# SIM7600CE.net
KiCad netlist of a schematic drawn in Altium Designer
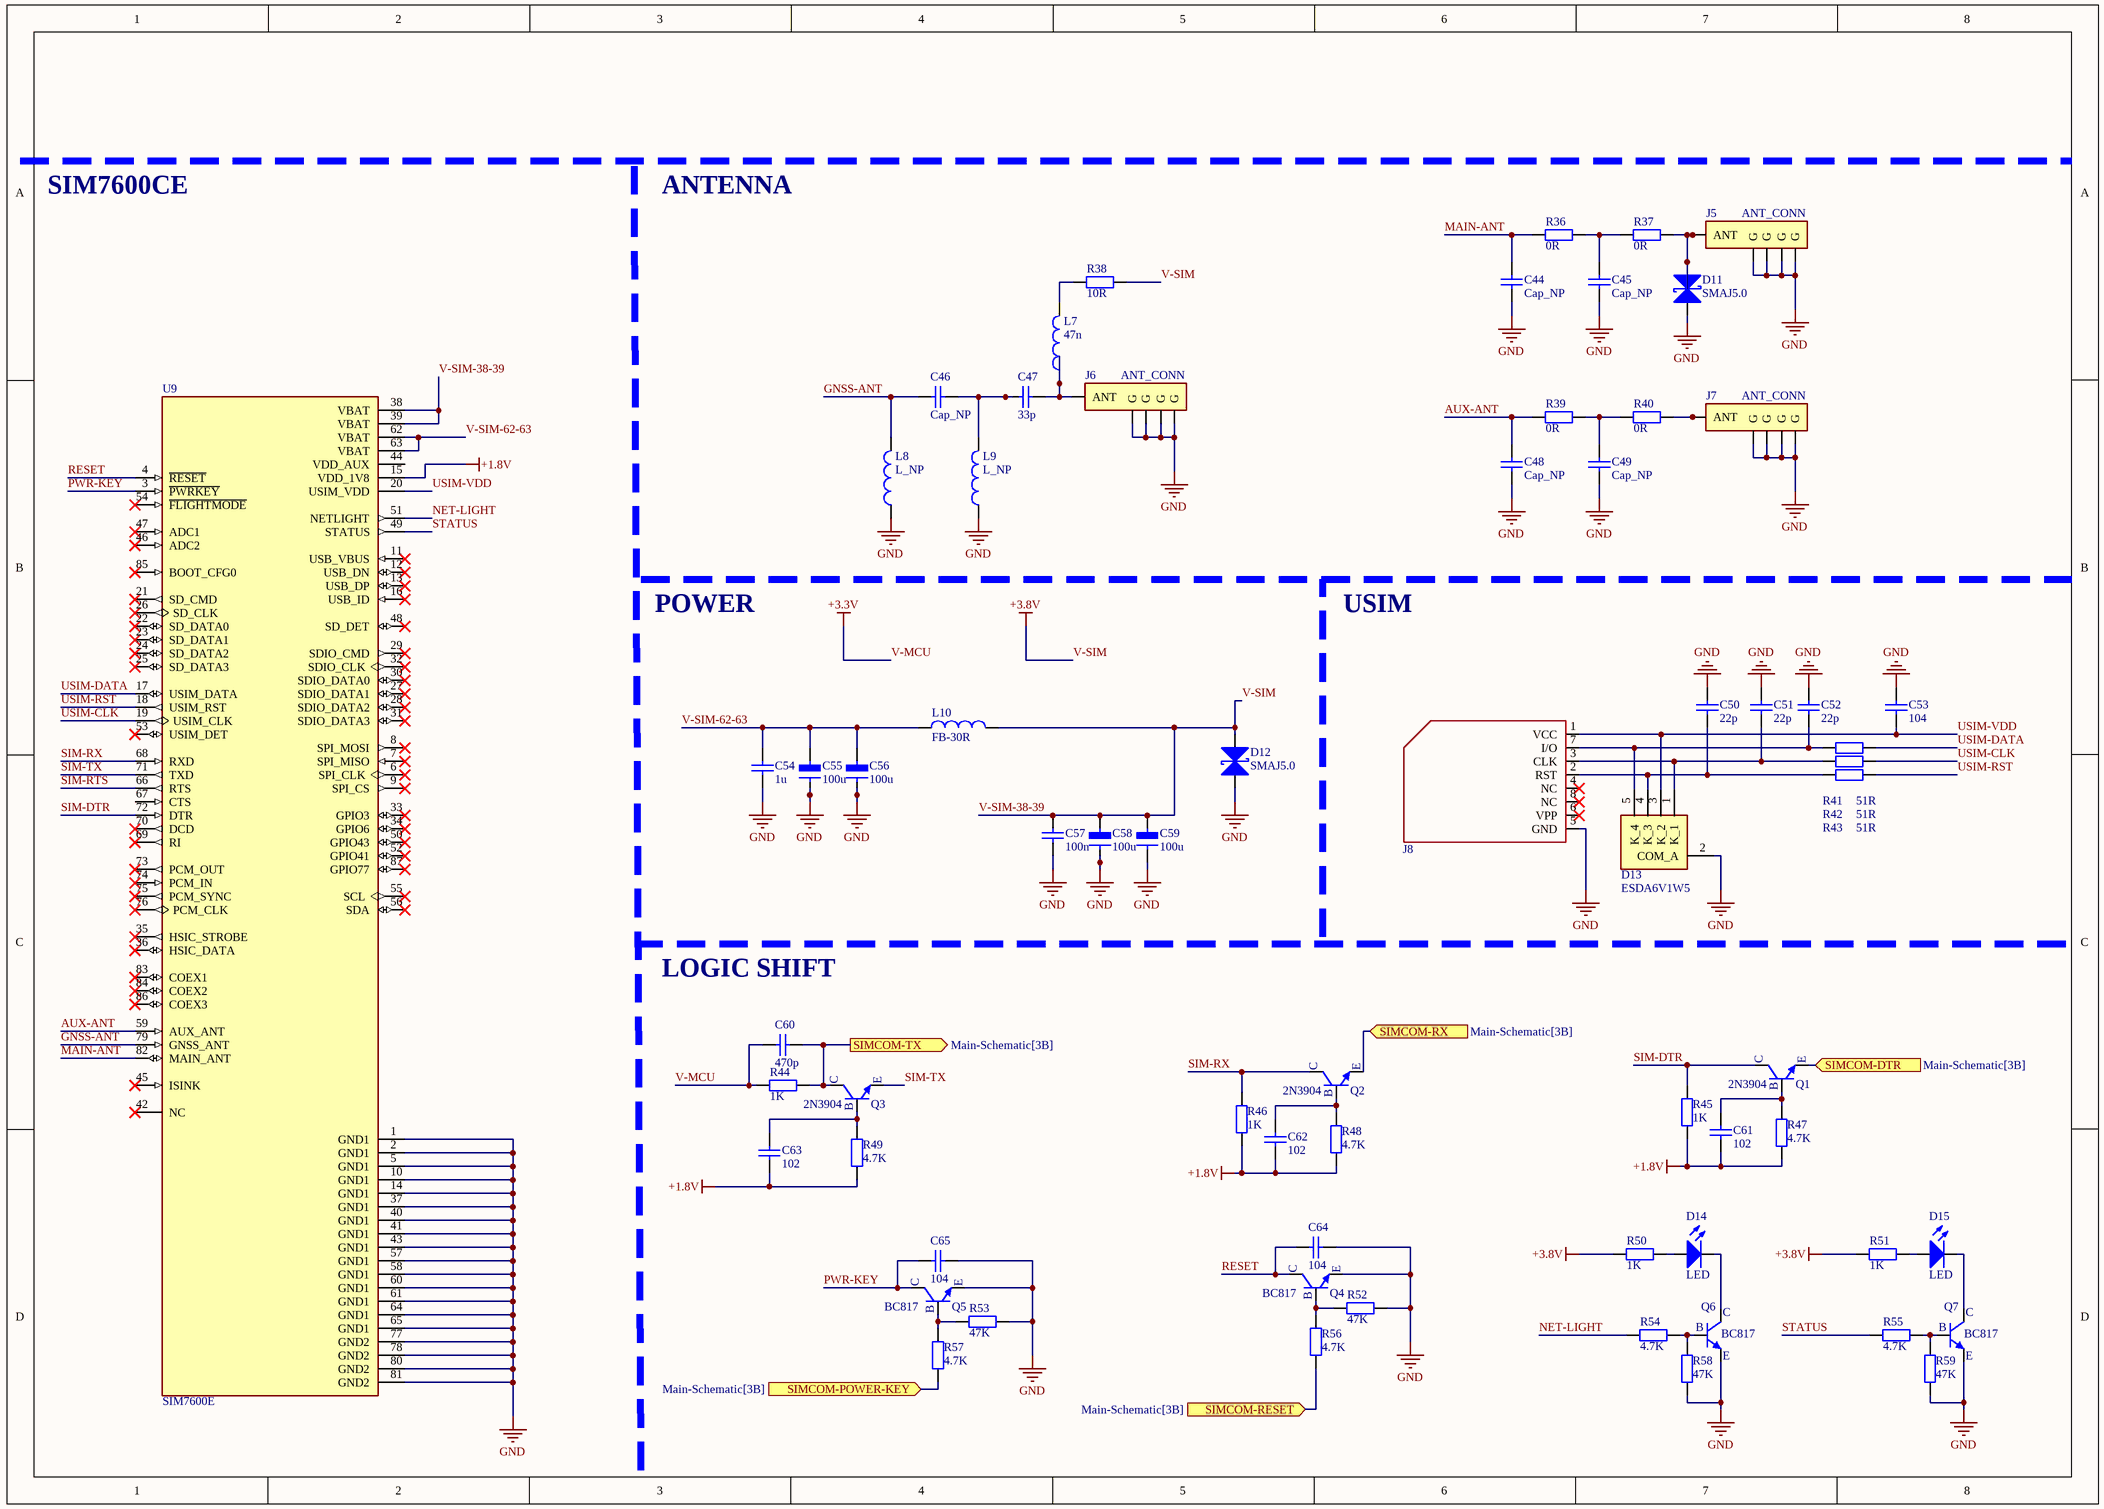
[diagram p0: SIM7600CE.SchDoc]

(export (version "E")
  (design (tool "Eeschema 10.0.6"))
  (components
    (comp (ref "C44")
      (value "Cap_NP")
      (footprint "CAP_0603")
      (description "Non-polarized capacitor")
      (libsource (lib "Capacitor") (part "Cap_NP"))
    )
    (comp (ref "C45")
      (value "Cap_NP")
      (footprint "CAP_0603")
      (description "Non-polarized capacitor")
      (libsource (lib "Capacitor") (part "Cap_NP"))
    )
    (comp (ref "C46")
      (value "Cap_NP")
      (footprint "CAP_0603")
      (description "Non-polarized capacitor")
      (libsource (lib "Capacitor") (part "Cap_NP"))
    )
    (comp (ref "C47")
      (value "33p")
      (footprint "CAP_0603")
      (description "Non-polarized capacitor")
      (libsource (lib "Capacitor") (part "Cap_NP"))
    )
    (comp (ref "C48")
      (value "Cap_NP")
      (footprint "CAP_0603")
      (description "Non-polarized capacitor")
      (libsource (lib "Capacitor") (part "Cap_NP"))
    )
    (comp (ref "C49")
      (value "Cap_NP")
      (footprint "CAP_0603")
      (description "Non-polarized capacitor")
      (libsource (lib "Capacitor") (part "Cap_NP"))
    )
    (comp (ref "C50")
      (value "22p")
      (footprint "CAP_0603")
      (description "Non-polarized capacitor")
      (libsource (lib "Capacitor") (part "Cap_NP"))
    )
    (comp (ref "C51")
      (value "22p")
      (footprint "CAP_0603")
      (description "Non-polarized capacitor")
      (libsource (lib "Capacitor") (part "Cap_NP"))
    )
    (comp (ref "C52")
      (value "22p")
      (footprint "CAP_0603")
      (description "Non-polarized capacitor")
      (libsource (lib "Capacitor") (part "Cap_NP"))
    )
    (comp (ref "C53")
      (value "104")
      (footprint "CAP_0603")
      (description "Non-polarized capacitor")
      (libsource (lib "Capacitor") (part "Cap_NP"))
    )
    (comp (ref "C54")
      (value "1u")
      (footprint "CAP_0603")
      (description "Non-polarized capacitor")
      (libsource (lib "Capacitor") (part "Cap_NP"))
    )
    (comp (ref "C55")
      (value "100u")
      (footprint "C_Tanta_B3528")
      (description "Polarized tantaLum capacitor")
      (libsource (lib "Capacitor") (part "Cap_Tatan"))
    )
    (comp (ref "C56")
      (value "100u")
      (footprint "C_Tanta_B3528")
      (description "Polarized tantaLum capacitor")
      (libsource (lib "Capacitor") (part "Cap_Tatan"))
    )
    (comp (ref "C57")
      (value "100n")
      (footprint "CAP_0603")
      (description "Non-polarized capacitor")
      (libsource (lib "Capacitor") (part "Cap_NP"))
    )
    (comp (ref "C58")
      (value "100u")
      (footprint "C_Tanta_B3528")
      (description "Polarized tantaLum capacitor")
      (libsource (lib "Capacitor") (part "Cap_Tatan"))
    )
    (comp (ref "C59")
      (value "100u")
      (footprint "C_Tanta_B3528")
      (description "Polarized tantaLum capacitor")
      (libsource (lib "Capacitor") (part "Cap_Tatan"))
    )
    (comp (ref "C60")
      (value "470p")
      (footprint "CAP_0603")
      (description "Non-polarized capacitor")
      (libsource (lib "Capacitor") (part "Cap_NP"))
    )
    (comp (ref "C61")
      (value "102")
      (footprint "CAP_0603")
      (description "Non-polarized capacitor")
      (libsource (lib "Capacitor") (part "Cap_NP"))
    )
    (comp (ref "C62")
      (value "102")
      (footprint "CAP_0603")
      (description "Non-polarized capacitor")
      (libsource (lib "Capacitor") (part "Cap_NP"))
    )
    (comp (ref "C63")
      (value "102")
      (footprint "CAP_0603")
      (description "Non-polarized capacitor")
      (libsource (lib "Capacitor") (part "Cap_NP"))
    )
    (comp (ref "C64")
      (value "104")
      (footprint "CAP_0603")
      (description "Non-polarized capacitor")
      (libsource (lib "Capacitor") (part "Cap_NP"))
    )
    (comp (ref "C65")
      (value "104")
      (footprint "CAP_0603")
      (description "Non-polarized capacitor")
      (libsource (lib "Capacitor") (part "Cap_NP"))
    )
    (comp (ref "D11")
      (value "SMAJ5.0")
      (footprint "SMA")
      (description "TVS diode")
      (libsource (lib "Diode") (part "TVS-Diode"))
    )
    (comp (ref "D12")
      (value "SMAJ5.0")
      (footprint "SMA")
      (description "TVS diode")
      (libsource (lib "Diode") (part "TVS-Diode"))
    )
    (comp (ref "D13")
      (value "ESDA6V1W5")
      (footprint "SOT65P210X110-5N")
      (description "Integrated Circuit")
      (fields (field (name "MOUSER PART NUMBER") "511-ESDA6V1W5"))
      (libsource (lib "SamacSys") (part "ESDA6V1W5"))
    )
    (comp (ref "D14")
      (value "LED")
      (footprint "LED-0805-Red")
      (description "Light Emitting Diode")
      (libsource (lib "Diode") (part "LED"))
    )
    (comp (ref "D15")
      (value "LED")
      (footprint "LED-0805-Red")
      (description "Light Emitting Diode")
      (libsource (lib "Diode") (part "LED"))
    )
    (comp (ref "J5")
      (value "ANT_CONN")
      (footprint "IPEX")
      (description "ATENNA PIN 1")
      (libsource (lib "Connector") (part "ANT_CONN"))
    )
    (comp (ref "J6")
      (value "ANT_CONN")
      (footprint "IPEX")
      (description "ATENNA PIN 1")
      (libsource (lib "Connector") (part "ANT_CONN"))
    )
    (comp (ref "J7")
      (value "ANT_CONN")
      (footprint "IPEX")
      (description "ATENNA PIN 1")
      (libsource (lib "Connector") (part "ANT_CONN"))
    )
    (comp (ref "J8")
      (value "MicroSimcard")
      (footprint "MICRO SIM SOCKET")
      (description "Micro Simcard Socket")
      (libsource (lib "VNT.Connector Socket") (part "MicroSimcard"))
    )
    (comp (ref "L7")
      (value "47n")
      (footprint "INDC-0805")
      (description "Inductor")
      (fields (field (name "PUBLISHER") "Altium Limited"))
      (libsource (lib "Inductor") (part "Inductor"))
    )
    (comp (ref "L8")
      (value "L_NP")
      (footprint "INDC-0805")
      (description "Inductor")
      (fields (field (name "PUBLISHER") "Altium Limited"))
      (libsource (lib "Inductor") (part "Inductor"))
    )
    (comp (ref "L9")
      (value "L_NP")
      (footprint "INDC-0805")
      (description "Inductor")
      (fields (field (name "PUBLISHER") "Altium Limited"))
      (libsource (lib "Inductor") (part "Inductor"))
    )
    (comp (ref "L10")
      (value "FB-30R")
      (footprint "INDC-0805")
      (description "Inductor")
      (fields (field (name "PUBLISHER") "Altium Limited"))
      (libsource (lib "Inductor") (part "Inductor"))
    )
    (comp (ref "Q1")
      (value "2N3904")
      (footprint "SOT-23")
      (libsource (lib "Transistor-FET-IGBT") (part "N-Trans"))
    )
    (comp (ref "Q2")
      (value "2N3904")
      (footprint "SOT-23")
      (libsource (lib "Transistor-FET-IGBT") (part "N-Trans"))
    )
    (comp (ref "Q3")
      (value "2N3904")
      (footprint "SOT-23")
      (libsource (lib "Transistor-FET-IGBT") (part "N-Trans"))
    )
    (comp (ref "Q4")
      (value "BC817")
      (footprint "SOT-23")
      (libsource (lib "Transistor-FET-IGBT") (part "N-Trans"))
    )
    (comp (ref "Q5")
      (value "BC817")
      (footprint "SOT-23")
      (libsource (lib "Transistor-FET-IGBT") (part "N-Trans"))
    )
    (comp (ref "Q6")
      (value "BC817")
      (footprint "SOT-23")
      (libsource (lib "Transistor-FET-IGBT") (part "N-Trans"))
    )
    (comp (ref "Q7")
      (value "BC817")
      (footprint "SOT-23")
      (libsource (lib "Transistor-FET-IGBT") (part "N-Trans"))
    )
    (comp (ref "R36") (value "0R") (footprint "RES_0603") (libsource (lib "") (part "Resistor_2")))
    (comp (ref "R37") (value "0R") (footprint "RES_0603") (libsource (lib "") (part "Resistor_2")))
    (comp (ref "R38") (value "10R") (footprint "RES_0603") (libsource (lib "Resistor") (part "Resistor")))
    (comp (ref "R39") (value "0R") (footprint "RES_0603") (libsource (lib "") (part "Resistor_2")))
    (comp (ref "R40") (value "0R") (footprint "RES_0603") (libsource (lib "") (part "Resistor_2")))
    (comp (ref "R41") (value "51R") (footprint "RES_0603") (libsource (lib "") (part "Resistor_2")))
    (comp (ref "R42") (value "51R") (footprint "RES_0603") (libsource (lib "") (part "Resistor_2")))
    (comp (ref "R43") (value "51R") (footprint "RES_0603") (libsource (lib "") (part "Resistor_2")))
    (comp (ref "R44") (value "1K") (footprint "RES_0603") (libsource (lib "Resistor") (part "Resistor")))
    (comp (ref "R45") (value "1K") (footprint "RES_0603") (libsource (lib "") (part "Resistor_1")))
    (comp (ref "R46") (value "1K") (footprint "RES_0603") (libsource (lib "") (part "Resistor_1")))
    (comp (ref "R47") (value "4.7K") (footprint "RES_0603") (libsource (lib "") (part "Resistor_1")))
    (comp (ref "R48") (value "4.7K") (footprint "RES_0603") (libsource (lib "") (part "Resistor_1")))
    (comp (ref "R49") (value "4.7K") (footprint "RES_0603") (libsource (lib "") (part "Resistor_1")))
    (comp (ref "R50") (value "1K") (footprint "RES_0603") (libsource (lib "Resistor") (part "Resistor")))
    (comp (ref "R51") (value "1K") (footprint "RES_0603") (libsource (lib "Resistor") (part "Resistor")))
    (comp (ref "R52") (value "47K") (footprint "RES_0603") (libsource (lib "") (part "Resistor_2")))
    (comp (ref "R53") (value "47K") (footprint "RES_0603") (libsource (lib "") (part "Resistor_2")))
    (comp (ref "R54") (value "4.7K") (footprint "RES_0603") (libsource (lib "Resistor") (part "Resistor")))
    (comp (ref "R55") (value "4.7K") (footprint "RES_0603") (libsource (lib "Resistor") (part "Resistor")))
    (comp (ref "R56") (value "4.7K") (footprint "RES_0603") (libsource (lib "") (part "Resistor_1")))
    (comp (ref "R57") (value "4.7K") (footprint "RES_0603") (libsource (lib "") (part "Resistor_1")))
    (comp (ref "R58") (value "47K") (footprint "RES_0603") (libsource (lib "") (part "Resistor_1")))
    (comp (ref "R59") (value "47K") (footprint "RES_0603") (libsource (lib "") (part "Resistor_1")))
    (comp (ref "U9")
      (value "SIM7600E")
      (footprint "XCVR_SIM7600E")
      (fields (field (name "MF") "SIMCom Wireless Solutions Limited"))
      (libsource (lib "SIM7600CE") (part "SIM7600E"))
    )
  )
  (nets
    (net (code "1") (name "+1.8V") (class "Default")
      (node (ref "C61") (pin "1") (pinfunction "1_1") (pintype "passive"))
      (node (ref "C62") (pin "1") (pinfunction "1_1") (pintype "passive"))
      (node (ref "C63") (pin "1") (pinfunction "1_1") (pintype "passive"))
      (node (ref "R45") (pin "1") (pinfunction "1_1") (pintype "passive"))
      (node (ref "R46") (pin "1") (pinfunction "1_1") (pintype "passive"))
      (node (ref "R47") (pin "1") (pinfunction "1_1") (pintype "passive"))
      (node (ref "R48") (pin "1") (pinfunction "1_1") (pintype "passive"))
      (node (ref "R49") (pin "1") (pinfunction "1_1") (pintype "passive"))
      (node (ref "U9") (pin "15") (pinfunction "VDD_1V8_15") (pintype "power_in"))
    )
    (net (code "2") (name "+3.3V") (class "Default")
      (node (ref "C60") (pin "2") (pinfunction "2_2") (pintype "passive"))
      (node (ref "R44") (pin "2") (pinfunction "2_2") (pintype "passive"))
    )
    (net (code "3") (name "+3.8V") (class "Default")
      (node (ref "C57") (pin "2") (pinfunction "2_2") (pintype "passive"))
      (node (ref "C58") (pin "1") (pinfunction "1_1") (pintype "passive"))
      (node (ref "C59") (pin "1") (pinfunction "1_1") (pintype "passive"))
      (node (ref "D12") (pin "2") (pinfunction "A_2") (pintype "passive"))
      (node (ref "L10") (pin "2") (pinfunction "2_2") (pintype "passive"))
      (node (ref "R38") (pin "1") (pinfunction "1_1") (pintype "passive"))
      (node (ref "R50") (pin "2") (pinfunction "2_2") (pintype "passive"))
      (node (ref "R51") (pin "2") (pinfunction "2_2") (pintype "passive"))
      (node (ref "U9") (pin "38") (pinfunction "VBAT_38") (pintype "power_in"))
      (node (ref "U9") (pin "39") (pinfunction "VBAT_39") (pintype "power_in"))
    )
    (net (code "4") (name "/AUX-ANT") (class "Default")
      (node (ref "C48") (pin "2") (pinfunction "2_2") (pintype "passive"))
      (node (ref "R39") (pin "1") (pinfunction "1_1") (pintype "passive"))
      (node (ref "U9") (pin "59") (pinfunction "AUX_ANT_59") (pintype "input"))
    )
    (net (code "5") (name "/GNSS-ANT") (class "Default")
      (node (ref "C46") (pin "2") (pinfunction "2_2") (pintype "passive"))
      (node (ref "L8") (pin "2") (pinfunction "2_2") (pintype "passive"))
      (node (ref "U9") (pin "79") (pinfunction "GNSS_ANT_79") (pintype "input"))
    )
    (net (code "6") (name "/MAIN-ANT") (class "Default")
      (node (ref "C44") (pin "2") (pinfunction "2_2") (pintype "passive"))
      (node (ref "R36") (pin "1") (pinfunction "1_1") (pintype "passive"))
      (node (ref "U9") (pin "82") (pinfunction "MAIN_ANT_82") (pintype "bidirectional"))
    )
    (net (code "7") (name "/NET-LIGHT") (class "Default")
      (node (ref "R54") (pin "2") (pinfunction "2_2") (pintype "passive"))
      (node (ref "U9") (pin "51") (pinfunction "NETLIGHT_51") (pintype "output"))
    )
    (net (code "8") (name "/PWR-KEY") (class "Default")
      (node (ref "C65") (pin "1") (pinfunction "1_1") (pintype "passive"))
      (node (ref "Q5") (pin "2") (pinfunction "C_2") (pintype "passive"))
      (node (ref "U9") (pin "3") (pinfunction "~{PWRKEY}_3") (pintype "input"))
    )
    (net (code "9") (name "/RESET") (class "Default")
      (node (ref "C64") (pin "1") (pinfunction "1_1") (pintype "passive"))
      (node (ref "Q4") (pin "2") (pinfunction "C_2") (pintype "passive"))
      (node (ref "U9") (pin "4") (pinfunction "~{RESET}_4") (pintype "input"))
    )
    (net (code "10") (name "/SIM-DTR") (class "Default")
      (node (ref "Q1") (pin "2") (pinfunction "C_2") (pintype "passive"))
      (node (ref "R45") (pin "2") (pinfunction "2_2") (pintype "passive"))
      (node (ref "U9") (pin "72") (pinfunction "DTR_72") (pintype "input"))
    )
    (net (code "11") (name "/SIM-RTS") (class "Default")
      (node (ref "U9") (pin "66") (pinfunction "RTS_66") (pintype "output"))
    )
    (net (code "12") (name "/SIM-RX") (class "Default")
      (node (ref "Q2") (pin "2") (pinfunction "C_2") (pintype "passive"))
      (node (ref "R46") (pin "2") (pinfunction "2_2") (pintype "passive"))
      (node (ref "U9") (pin "68") (pinfunction "RXD_68") (pintype "input"))
    )
    (net (code "13") (name "/SIM-TX") (class "Default")
      (node (ref "Q3") (pin "3") (pinfunction "E_3") (pintype "passive"))
      (node (ref "U9") (pin "71") (pinfunction "TXD_71") (pintype "output"))
    )
    (net (code "14") (name "/SIMCOM-DTR") (class "Default")
      (node (ref "Q1") (pin "3") (pinfunction "E_3") (pintype "passive"))
    )
    (net (code "15") (name "/SIMCOM-POWER-KEY") (class "Default")
      (node (ref "R57") (pin "1") (pinfunction "1_1") (pintype "passive"))
    )
    (net (code "16") (name "/SIMCOM-RESET") (class "Default")
      (node (ref "R56") (pin "1") (pinfunction "1_1") (pintype "passive"))
    )
    (net (code "17") (name "/SIMCOM-RX") (class "Default")
      (node (ref "Q2") (pin "3") (pinfunction "E_3") (pintype "passive"))
    )
    (net (code "18") (name "/SIMCOM-TX") (class "Default")
      (node (ref "C60") (pin "1") (pinfunction "1_1") (pintype "passive"))
      (node (ref "Q3") (pin "2") (pinfunction "C_2") (pintype "passive"))
      (node (ref "R44") (pin "1") (pinfunction "1_1") (pintype "passive"))
    )
    (net (code "19") (name "/STATUS") (class "Default")
      (node (ref "R55") (pin "2") (pinfunction "2_2") (pintype "passive"))
      (node (ref "U9") (pin "49") (pinfunction "STATUS_49") (pintype "output"))
    )
    (net (code "20") (name "/USIM-CLK") (class "Default")
      (node (ref "R42") (pin "2") (pinfunction "2_2") (pintype "passive"))
      (node (ref "U9") (pin "19") (pinfunction "USIM_CLK_19") (pintype "output"))
    )
    (net (code "21") (name "/USIM-DATA") (class "Default")
      (node (ref "R41") (pin "2") (pinfunction "2_2") (pintype "passive"))
      (node (ref "U9") (pin "17") (pinfunction "USIM_DATA_17") (pintype "bidirectional"))
    )
    (net (code "22") (name "/USIM-RST") (class "Default")
      (node (ref "R43") (pin "2") (pinfunction "2_2") (pintype "passive"))
      (node (ref "U9") (pin "18") (pinfunction "USIM_RST_18") (pintype "output"))
    )
    (net (code "23") (name "/USIM-VDD") (class "Default")
      (node (ref "C53") (pin "1") (pinfunction "1_1") (pintype "passive"))
      (node (ref "D13") (pin "3") (pinfunction "K_2_3") (pintype "passive"))
      (node (ref "J8") (pin "1") (pinfunction "VCC_1") (pintype "passive"))
      (node (ref "U9") (pin "20") (pinfunction "USIM_VDD_20") (pintype "power_in"))
    )
    (net (code "24") (name "/V-SIM-62-63") (class "Default")
      (node (ref "C54") (pin "2") (pinfunction "2_2") (pintype "passive"))
      (node (ref "C55") (pin "1") (pinfunction "1_1") (pintype "passive"))
      (node (ref "C56") (pin "1") (pinfunction "1_1") (pintype "passive"))
      (node (ref "L10") (pin "1") (pinfunction "1_1") (pintype "passive"))
      (node (ref "U9") (pin "62") (pinfunction "VBAT_62") (pintype "power_in"))
      (node (ref "U9") (pin "63") (pinfunction "VBAT_63") (pintype "power_in"))
    )
    (net (code "25") (name "GND") (class "Default")
      (node (ref "C44") (pin "1") (pinfunction "1_1") (pintype "passive"))
      (node (ref "C45") (pin "1") (pinfunction "1_1") (pintype "passive"))
      (node (ref "C48") (pin "1") (pinfunction "1_1") (pintype "passive"))
      (node (ref "C49") (pin "1") (pinfunction "1_1") (pintype "passive"))
      (node (ref "C50") (pin "2") (pinfunction "2_2") (pintype "passive"))
      (node (ref "C51") (pin "2") (pinfunction "2_2") (pintype "passive"))
      (node (ref "C52") (pin "2") (pinfunction "2_2") (pintype "passive"))
      (node (ref "C53") (pin "2") (pinfunction "2_2") (pintype "passive"))
      (node (ref "C54") (pin "1") (pinfunction "1_1") (pintype "passive"))
      (node (ref "C55") (pin "2") (pinfunction "2_2") (pintype "passive"))
      (node (ref "C56") (pin "2") (pinfunction "2_2") (pintype "passive"))
      (node (ref "C57") (pin "1") (pinfunction "1_1") (pintype "passive"))
      (node (ref "C58") (pin "2") (pinfunction "2_2") (pintype "passive"))
      (node (ref "C59") (pin "2") (pinfunction "2_2") (pintype "passive"))
      (node (ref "C64") (pin "2") (pinfunction "2_2") (pintype "passive"))
      (node (ref "C65") (pin "2") (pinfunction "2_2") (pintype "passive"))
      (node (ref "D11") (pin "1") (pinfunction "K_1") (pintype "passive"))
      (node (ref "D12") (pin "1") (pinfunction "K_1") (pintype "passive"))
      (node (ref "D13") (pin "2") (pinfunction "COM_A_2") (pintype "passive"))
      (node (ref "J5") (pin "2") (pinfunction "G_2") (pintype "passive"))
      (node (ref "J5") (pin "3") (pinfunction "G_3") (pintype "passive"))
      (node (ref "J5") (pin "4") (pinfunction "G_4") (pintype "passive"))
      (node (ref "J5") (pin "5") (pinfunction "G_5") (pintype "passive"))
      (node (ref "J6") (pin "2") (pinfunction "G_2") (pintype "passive"))
      (node (ref "J6") (pin "3") (pinfunction "G_3") (pintype "passive"))
      (node (ref "J6") (pin "4") (pinfunction "G_4") (pintype "passive"))
      (node (ref "J6") (pin "5") (pinfunction "G_5") (pintype "passive"))
      (node (ref "J7") (pin "2") (pinfunction "G_2") (pintype "passive"))
      (node (ref "J7") (pin "3") (pinfunction "G_3") (pintype "passive"))
      (node (ref "J7") (pin "4") (pinfunction "G_4") (pintype "passive"))
      (node (ref "J7") (pin "5") (pinfunction "G_5") (pintype "passive"))
      (node (ref "J8") (pin "5") (pinfunction "GND_5") (pintype "passive"))
      (node (ref "L8") (pin "1") (pinfunction "1_1") (pintype "passive"))
      (node (ref "L9") (pin "1") (pinfunction "1_1") (pintype "passive"))
      (node (ref "Q4") (pin "3") (pinfunction "E_3") (pintype "passive"))
      (node (ref "Q5") (pin "3") (pinfunction "E_3") (pintype "passive"))
      (node (ref "Q6") (pin "3") (pinfunction "E_3") (pintype "passive"))
      (node (ref "Q7") (pin "3") (pinfunction "E_3") (pintype "passive"))
      (node (ref "R52") (pin "2") (pinfunction "2_2") (pintype "passive"))
      (node (ref "R53") (pin "2") (pinfunction "2_2") (pintype "passive"))
      (node (ref "R58") (pin "1") (pinfunction "1_1") (pintype "passive"))
      (node (ref "R59") (pin "1") (pinfunction "1_1") (pintype "passive"))
      (node (ref "U9") (pin "1") (pinfunction "GND1_1") (pintype "power_in"))
      (node (ref "U9") (pin "10") (pinfunction "GND1_10") (pintype "power_in"))
      (node (ref "U9") (pin "14") (pinfunction "GND1_14") (pintype "power_in"))
      (node (ref "U9") (pin "2") (pinfunction "GND1_2") (pintype "power_in"))
      (node (ref "U9") (pin "37") (pinfunction "GND1_37") (pintype "power_in"))
      (node (ref "U9") (pin "40") (pinfunction "GND1_40") (pintype "power_in"))
      (node (ref "U9") (pin "41") (pinfunction "GND1_41") (pintype "power_in"))
      (node (ref "U9") (pin "43") (pinfunction "GND1_43") (pintype "power_in"))
      (node (ref "U9") (pin "5") (pinfunction "GND1_5") (pintype "power_in"))
      (node (ref "U9") (pin "57") (pinfunction "GND1_57") (pintype "power_in"))
      (node (ref "U9") (pin "58") (pinfunction "GND1_58") (pintype "power_in"))
      (node (ref "U9") (pin "60") (pinfunction "GND1_60") (pintype "power_in"))
      (node (ref "U9") (pin "61") (pinfunction "GND1_61") (pintype "power_in"))
      (node (ref "U9") (pin "64") (pinfunction "GND1_64") (pintype "power_in"))
      (node (ref "U9") (pin "65") (pinfunction "GND1_65") (pintype "power_in"))
      (node (ref "U9") (pin "77") (pinfunction "GND2_77") (pintype "power_in"))
      (node (ref "U9") (pin "78") (pinfunction "GND2_78") (pintype "power_in"))
      (node (ref "U9") (pin "80") (pinfunction "GND2_80") (pintype "power_in"))
      (node (ref "U9") (pin "81") (pinfunction "GND2_81") (pintype "power_in"))
    )
    (net (code "26") (name "Net-(C45-Pad2)") (class "Default")
      (node (ref "C45") (pin "2") (pinfunction "2_2") (pintype "passive"))
      (node (ref "R36") (pin "2") (pinfunction "2_2") (pintype "passive"))
      (node (ref "R37") (pin "1") (pinfunction "1_1") (pintype "passive"))
    )
    (net (code "27") (name "Net-(C46-Pad1)") (class "Default")
      (node (ref "C46") (pin "1") (pinfunction "1_1") (pintype "passive"))
      (node (ref "C47") (pin "2") (pinfunction "2_2") (pintype "passive"))
      (node (ref "L9") (pin "2") (pinfunction "2_2") (pintype "passive"))
    )
    (net (code "28") (name "Net-(C49-Pad2)") (class "Default")
      (node (ref "C49") (pin "2") (pinfunction "2_2") (pintype "passive"))
      (node (ref "R39") (pin "2") (pinfunction "2_2") (pintype "passive"))
      (node (ref "R40") (pin "1") (pinfunction "1_1") (pintype "passive"))
    )
    (net (code "29") (name "Net-(D11-A)") (class "Default")
      (node (ref "D11") (pin "2") (pinfunction "A_2") (pintype "passive"))
      (node (ref "J5") (pin "1") (pinfunction "ANT_1") (pintype "passive"))
      (node (ref "R37") (pin "2") (pinfunction "2_2") (pintype "passive"))
    )
    (net (code "30") (name "Net-(D13-K_1)") (class "Default")
      (node (ref "C51") (pin "1") (pinfunction "1_1") (pintype "passive"))
      (node (ref "D13") (pin "1") (pinfunction "K_1_1") (pintype "passive"))
      (node (ref "J8") (pin "3") (pinfunction "CLK_3") (pintype "passive"))
      (node (ref "R42") (pin "1") (pinfunction "1_1") (pintype "passive"))
    )
    (net (code "31") (name "Net-(D13-K_3)") (class "Default")
      (node (ref "C50") (pin "1") (pinfunction "1_1") (pintype "passive"))
      (node (ref "D13") (pin "4") (pinfunction "K_3_4") (pintype "passive"))
      (node (ref "J8") (pin "2") (pinfunction "RST_2") (pintype "passive"))
      (node (ref "R43") (pin "1") (pinfunction "1_1") (pintype "passive"))
    )
    (net (code "32") (name "Net-(D13-K_4)") (class "Default")
      (node (ref "C52") (pin "1") (pinfunction "1_1") (pintype "passive"))
      (node (ref "D13") (pin "5") (pinfunction "K_4_5") (pintype "passive"))
      (node (ref "J8") (pin "7") (pinfunction "I/O_7") (pintype "passive"))
      (node (ref "R41") (pin "1") (pinfunction "1_1") (pintype "passive"))
    )
    (net (code "33") (name "Net-(D14-A)") (class "Default")
      (node (ref "D14") (pin "1") (pinfunction "A_1") (pintype "passive"))
      (node (ref "R50") (pin "1") (pinfunction "1_1") (pintype "passive"))
    )
    (net (code "34") (name "Net-(D14-K)") (class "Default")
      (node (ref "D14") (pin "2") (pinfunction "K_2") (pintype "passive"))
      (node (ref "Q6") (pin "2") (pinfunction "C_2") (pintype "passive"))
    )
    (net (code "35") (name "Net-(D15-A)") (class "Default")
      (node (ref "D15") (pin "1") (pinfunction "A_1") (pintype "passive"))
      (node (ref "R51") (pin "1") (pinfunction "1_1") (pintype "passive"))
    )
    (net (code "36") (name "Net-(D15-K)") (class "Default")
      (node (ref "D15") (pin "2") (pinfunction "K_2") (pintype "passive"))
      (node (ref "Q7") (pin "2") (pinfunction "C_2") (pintype "passive"))
    )
    (net (code "37") (name "Net-(J6-ANT)") (class "Default")
      (node (ref "C47") (pin "1") (pinfunction "1_1") (pintype "passive"))
      (node (ref "J6") (pin "1") (pinfunction "ANT_1") (pintype "passive"))
      (node (ref "L7") (pin "1") (pinfunction "1_1") (pintype "passive"))
    )
    (net (code "38") (name "Net-(J7-ANT)") (class "Default")
      (node (ref "J7") (pin "1") (pinfunction "ANT_1") (pintype "passive"))
      (node (ref "R40") (pin "2") (pinfunction "2_2") (pintype "passive"))
    )
    (net (code "39") (name "Net-(L7-Pad2)") (class "Default")
      (node (ref "L7") (pin "2") (pinfunction "2_2") (pintype "passive"))
      (node (ref "R38") (pin "2") (pinfunction "2_2") (pintype "passive"))
    )
    (net (code "40") (name "Net-(Q1-B)") (class "Default")
      (node (ref "C61") (pin "2") (pinfunction "2_2") (pintype "passive"))
      (node (ref "Q1") (pin "1") (pinfunction "B_1") (pintype "passive"))
      (node (ref "R47") (pin "2") (pinfunction "2_2") (pintype "passive"))
    )
    (net (code "41") (name "Net-(Q2-B)") (class "Default")
      (node (ref "C62") (pin "2") (pinfunction "2_2") (pintype "passive"))
      (node (ref "Q2") (pin "1") (pinfunction "B_1") (pintype "passive"))
      (node (ref "R48") (pin "2") (pinfunction "2_2") (pintype "passive"))
    )
    (net (code "42") (name "Net-(Q3-B)") (class "Default")
      (node (ref "C63") (pin "2") (pinfunction "2_2") (pintype "passive"))
      (node (ref "Q3") (pin "1") (pinfunction "B_1") (pintype "passive"))
      (node (ref "R49") (pin "2") (pinfunction "2_2") (pintype "passive"))
    )
    (net (code "43") (name "Net-(Q4-B)") (class "Default")
      (node (ref "Q4") (pin "1") (pinfunction "B_1") (pintype "passive"))
      (node (ref "R52") (pin "1") (pinfunction "1_1") (pintype "passive"))
      (node (ref "R56") (pin "2") (pinfunction "2_2") (pintype "passive"))
    )
    (net (code "44") (name "Net-(Q5-B)") (class "Default")
      (node (ref "Q5") (pin "1") (pinfunction "B_1") (pintype "passive"))
      (node (ref "R53") (pin "1") (pinfunction "1_1") (pintype "passive"))
      (node (ref "R57") (pin "2") (pinfunction "2_2") (pintype "passive"))
    )
    (net (code "45") (name "Net-(Q6-B)") (class "Default")
      (node (ref "Q6") (pin "1") (pinfunction "B_1") (pintype "passive"))
      (node (ref "R54") (pin "1") (pinfunction "1_1") (pintype "passive"))
      (node (ref "R58") (pin "2") (pinfunction "2_2") (pintype "passive"))
    )
    (net (code "46") (name "Net-(Q7-B)") (class "Default")
      (node (ref "Q7") (pin "1") (pinfunction "B_1") (pintype "passive"))
      (node (ref "R55") (pin "1") (pinfunction "1_1") (pintype "passive"))
      (node (ref "R59") (pin "2") (pinfunction "2_2") (pintype "passive"))
    )
    (net (code "47") (name "unconnected-(J8-NC-Pad4)") (class "Default")
      (node (ref "J8") (pin "4") (pinfunction "NC_4") (pintype "passive+no_connect"))
    )
    (net (code "48") (name "unconnected-(J8-NC-Pad8)") (class "Default")
      (node (ref "J8") (pin "8") (pinfunction "NC_8") (pintype "passive+no_connect"))
    )
    (net (code "49") (name "unconnected-(J8-VPP-Pad6)") (class "Default")
      (node (ref "J8") (pin "6") (pinfunction "VPP_6") (pintype "passive+no_connect"))
    )
    (net (code "50") (name "unconnected-(U9-ADC1-Pad47)") (class "Default")
      (node (ref "U9") (pin "47") (pinfunction "ADC1_47") (pintype "input+no_connect"))
    )
    (net (code "51") (name "unconnected-(U9-ADC2-Pad46)") (class "Default")
      (node (ref "U9") (pin "46") (pinfunction "ADC2_46") (pintype "input+no_connect"))
    )
    (net (code "52") (name "unconnected-(U9-BOOT_CFG0-Pad85)") (class "Default")
      (node (ref "U9") (pin "85") (pinfunction "BOOT_CFG0_85") (pintype "input+no_connect"))
    )
    (net (code "53") (name "unconnected-(U9-COEX1-Pad83)") (class "Default")
      (node (ref "U9") (pin "83") (pinfunction "COEX1_83") (pintype "bidirectional+no_connect"))
    )
    (net (code "54") (name "unconnected-(U9-COEX2-Pad84)") (class "Default")
      (node (ref "U9") (pin "84") (pinfunction "COEX2_84") (pintype "bidirectional+no_connect"))
    )
    (net (code "55") (name "unconnected-(U9-COEX3-Pad86)") (class "Default")
      (node (ref "U9") (pin "86") (pinfunction "COEX3_86") (pintype "bidirectional+no_connect"))
    )
    (net (code "56") (name "unconnected-(U9-CTS-Pad67)") (class "Default")
      (node (ref "U9") (pin "67") (pinfunction "CTS_67") (pintype "input"))
    )
    (net (code "57") (name "unconnected-(U9-DCD-Pad70)") (class "Default")
      (node (ref "U9") (pin "70") (pinfunction "DCD_70") (pintype "output+no_connect"))
    )
    (net (code "58") (name "unconnected-(U9-GPIO3-Pad33)") (class "Default")
      (node (ref "U9") (pin "33") (pinfunction "GPIO3_33") (pintype "bidirectional+no_connect"))
    )
    (net (code "59") (name "unconnected-(U9-GPIO6-Pad34)") (class "Default")
      (node (ref "U9") (pin "34") (pinfunction "GPIO6_34") (pintype "bidirectional+no_connect"))
    )
    (net (code "60") (name "unconnected-(U9-GPIO41-Pad52)") (class "Default")
      (node (ref "U9") (pin "52") (pinfunction "GPIO41_52") (pintype "bidirectional+no_connect"))
    )
    (net (code "61") (name "unconnected-(U9-GPIO43-Pad50)") (class "Default")
      (node (ref "U9") (pin "50") (pinfunction "GPIO43_50") (pintype "bidirectional+no_connect"))
    )
    (net (code "62") (name "unconnected-(U9-GPIO77-Pad87)") (class "Default")
      (node (ref "U9") (pin "87") (pinfunction "GPIO77_87") (pintype "bidirectional+no_connect"))
    )
    (net (code "63") (name "unconnected-(U9-HSIC_DATA-Pad36)") (class "Default")
      (node (ref "U9") (pin "36") (pinfunction "HSIC_DATA_36") (pintype "bidirectional+no_connect"))
    )
    (net (code "64") (name "unconnected-(U9-HSIC_STROBE-Pad35)") (class "Default")
      (node (ref "U9") (pin "35") (pinfunction "HSIC_STROBE_35") (pintype "output+no_connect"))
    )
    (net (code "65") (name "unconnected-(U9-ISINK-Pad45)") (class "Default")
      (node (ref "U9") (pin "45") (pinfunction "ISINK_45") (pintype "input+no_connect"))
    )
    (net (code "66") (name "unconnected-(U9-NC-Pad42)") (class "Default")
      (node (ref "U9") (pin "42") (pinfunction "NC_42") (pintype "passive+no_connect"))
    )
    (net (code "67") (name "unconnected-(U9-PCM_CLK-Pad76)") (class "Default")
      (node (ref "U9") (pin "76") (pinfunction "PCM_CLK_76") (pintype "output+no_connect"))
    )
    (net (code "68") (name "unconnected-(U9-PCM_IN-Pad74)") (class "Default")
      (node (ref "U9") (pin "74") (pinfunction "PCM_IN_74") (pintype "input+no_connect"))
    )
    (net (code "69") (name "unconnected-(U9-PCM_OUT-Pad73)") (class "Default")
      (node (ref "U9") (pin "73") (pinfunction "PCM_OUT_73") (pintype "output+no_connect"))
    )
    (net (code "70") (name "unconnected-(U9-PCM_SYNC-Pad75)") (class "Default")
      (node (ref "U9") (pin "75") (pinfunction "PCM_SYNC_75") (pintype "output+no_connect"))
    )
    (net (code "71") (name "unconnected-(U9-RI-Pad69)") (class "Default")
      (node (ref "U9") (pin "69") (pinfunction "RI_69") (pintype "output+no_connect"))
    )
    (net (code "72") (name "unconnected-(U9-SCL-Pad55)") (class "Default")
      (node (ref "U9") (pin "55") (pinfunction "SCL_55") (pintype "output+no_connect"))
    )
    (net (code "73") (name "unconnected-(U9-SDA-Pad56)") (class "Default")
      (node (ref "U9") (pin "56") (pinfunction "SDA_56") (pintype "bidirectional+no_connect"))
    )
    (net (code "74") (name "unconnected-(U9-SDIO_CLK-Pad32)") (class "Default")
      (node (ref "U9") (pin "32") (pinfunction "SDIO_CLK_32") (pintype "output+no_connect"))
    )
    (net (code "75") (name "unconnected-(U9-SDIO_CMD-Pad29)") (class "Default")
      (node (ref "U9") (pin "29") (pinfunction "SDIO_CMD_29") (pintype "output+no_connect"))
    )
    (net (code "76") (name "unconnected-(U9-SDIO_DATA0-Pad30)") (class "Default")
      (node (ref "U9") (pin "30") (pinfunction "SDIO_DATA0_30") (pintype "bidirectional+no_connect"))
    )
    (net (code "77") (name "unconnected-(U9-SDIO_DATA1-Pad27)") (class "Default")
      (node (ref "U9") (pin "27") (pinfunction "SDIO_DATA1_27") (pintype "bidirectional+no_connect"))
    )
    (net (code "78") (name "unconnected-(U9-SDIO_DATA2-Pad28)") (class "Default")
      (node (ref "U9") (pin "28") (pinfunction "SDIO_DATA2_28") (pintype "bidirectional+no_connect"))
    )
    (net (code "79") (name "unconnected-(U9-SDIO_DATA3-Pad31)") (class "Default")
      (node (ref "U9") (pin "31") (pinfunction "SDIO_DATA3_31") (pintype "bidirectional+no_connect"))
    )
    (net (code "80") (name "unconnected-(U9-SD_CLK-Pad26)") (class "Default")
      (node (ref "U9") (pin "26") (pinfunction "SD_CLK_26") (pintype "output+no_connect"))
    )
    (net (code "81") (name "unconnected-(U9-SD_CMD-Pad21)") (class "Default")
      (node (ref "U9") (pin "21") (pinfunction "SD_CMD_21") (pintype "output+no_connect"))
    )
    (net (code "82") (name "unconnected-(U9-SD_DATA0-Pad22)") (class "Default")
      (node (ref "U9") (pin "22") (pinfunction "SD_DATA0_22") (pintype "bidirectional+no_connect"))
    )
    (net (code "83") (name "unconnected-(U9-SD_DATA1-Pad23)") (class "Default")
      (node (ref "U9") (pin "23") (pinfunction "SD_DATA1_23") (pintype "bidirectional+no_connect"))
    )
    (net (code "84") (name "unconnected-(U9-SD_DATA2-Pad24)") (class "Default")
      (node (ref "U9") (pin "24") (pinfunction "SD_DATA2_24") (pintype "bidirectional+no_connect"))
    )
    (net (code "85") (name "unconnected-(U9-SD_DATA3-Pad25)") (class "Default")
      (node (ref "U9") (pin "25") (pinfunction "SD_DATA3_25") (pintype "bidirectional+no_connect"))
    )
    (net (code "86") (name "unconnected-(U9-SD_DET-Pad48)") (class "Default")
      (node (ref "U9") (pin "48") (pinfunction "SD_DET_48") (pintype "bidirectional+no_connect"))
    )
    (net (code "87") (name "unconnected-(U9-SPI_CLK-Pad6)") (class "Default")
      (node (ref "U9") (pin "6") (pinfunction "SPI_CLK_6") (pintype "output+no_connect"))
    )
    (net (code "88") (name "unconnected-(U9-SPI_CS-Pad9)") (class "Default")
      (node (ref "U9") (pin "9") (pinfunction "SPI_CS_9") (pintype "output+no_connect"))
    )
    (net (code "89") (name "unconnected-(U9-SPI_MISO-Pad7)") (class "Default")
      (node (ref "U9") (pin "7") (pinfunction "SPI_MISO_7") (pintype "input+no_connect"))
    )
    (net (code "90") (name "unconnected-(U9-SPI_MOSI-Pad8)") (class "Default")
      (node (ref "U9") (pin "8") (pinfunction "SPI_MOSI_8") (pintype "output+no_connect"))
    )
    (net (code "91") (name "unconnected-(U9-USB_DN-Pad12)") (class "Default")
      (node (ref "U9") (pin "12") (pinfunction "USB_DN_12") (pintype "bidirectional+no_connect"))
    )
    (net (code "92") (name "unconnected-(U9-USB_DP-Pad13)") (class "Default")
      (node (ref "U9") (pin "13") (pinfunction "USB_DP_13") (pintype "bidirectional+no_connect"))
    )
    (net (code "93") (name "unconnected-(U9-USB_ID-Pad16)") (class "Default")
      (node (ref "U9") (pin "16") (pinfunction "USB_ID_16") (pintype "input+no_connect"))
    )
    (net (code "94") (name "unconnected-(U9-USB_VBUS-Pad11)") (class "Default")
      (node (ref "U9") (pin "11") (pinfunction "USB_VBUS_11") (pintype "input+no_connect"))
    )
    (net (code "95") (name "unconnected-(U9-USIM_DET-Pad53)") (class "Default")
      (node (ref "U9") (pin "53") (pinfunction "USIM_DET_53") (pintype "bidirectional+no_connect"))
    )
    (net (code "96") (name "unconnected-(U9-VDD_AUX-Pad44)") (class "Default")
      (node (ref "U9") (pin "44") (pinfunction "VDD_AUX_44") (pintype "power_in"))
    )
    (net (code "97") (name "unconnected-(U9-~{FLIGHTMODE}-Pad54)") (class "Default")
      (node (ref "U9") (pin "54") (pinfunction "~{FLIGHTMODE}_54") (pintype "input+no_connect"))
    )
  )
)
